# 1A20J12_1A21J13_A.net
KiCad netlist of a schematic drawn in Altium Designer
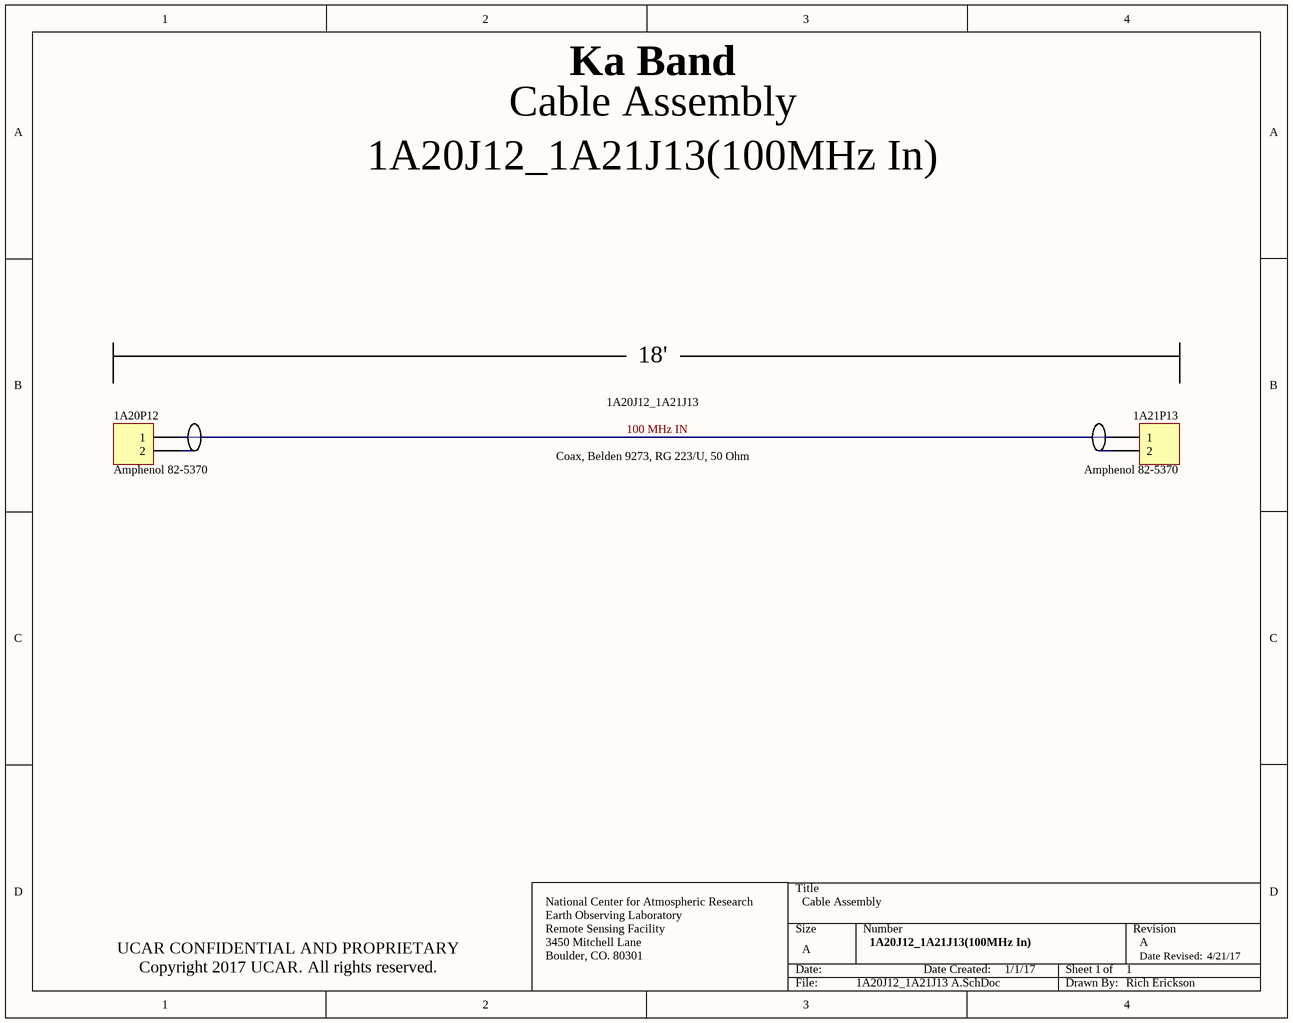
[diagram p0: 1A20J12_1A21J13 A.SchDoc]

(export (version "E")
  (design (tool "Eeschema 10.0.6"))
  (components
    (comp (ref "1A20P12")
      (value "Amphenol 82-5370")
      (footprint "HDR1X2")
      (description "Header, 2-Pin")
      (fields (field (name "PUBLISHER") "Altium Limited"))
      (libsource (lib "Miscellaneous Connectors") (part "Header 2"))
    )
    (comp (ref "1A21P13")
      (value "Amphenol 82-5370")
      (footprint "HDR1X2")
      (description "Header, 2-Pin")
      (fields (field (name "PUBLISHER") "Altium Limited"))
      (libsource (lib "") (part "Header 2_1"))
    )
  )
  (nets
    (net (code "1") (name "/100 MHz IN") (class "Default")
      (node (ref "1A20P12") (pin "1") (pinfunction "1_1") (pintype "passive"))
      (node (ref "1A21P13") (pin "1") (pinfunction "1_1") (pintype "passive"))
    )
    (net (code "2") (name "unconnected-(1A20P12-Pad2)") (class "Default")
      (node (ref "1A20P12") (pin "2") (pinfunction "2_2") (pintype "passive"))
    )
    (net (code "3") (name "unconnected-(1A21P13-Pad2)") (class "Default")
      (node (ref "1A21P13") (pin "2") (pinfunction "2_2") (pintype "passive"))
    )
  )
)
